# openSX70-dongle_v6-3-dual-led.net
KiCad netlist of a schematic drawn in EAGLE
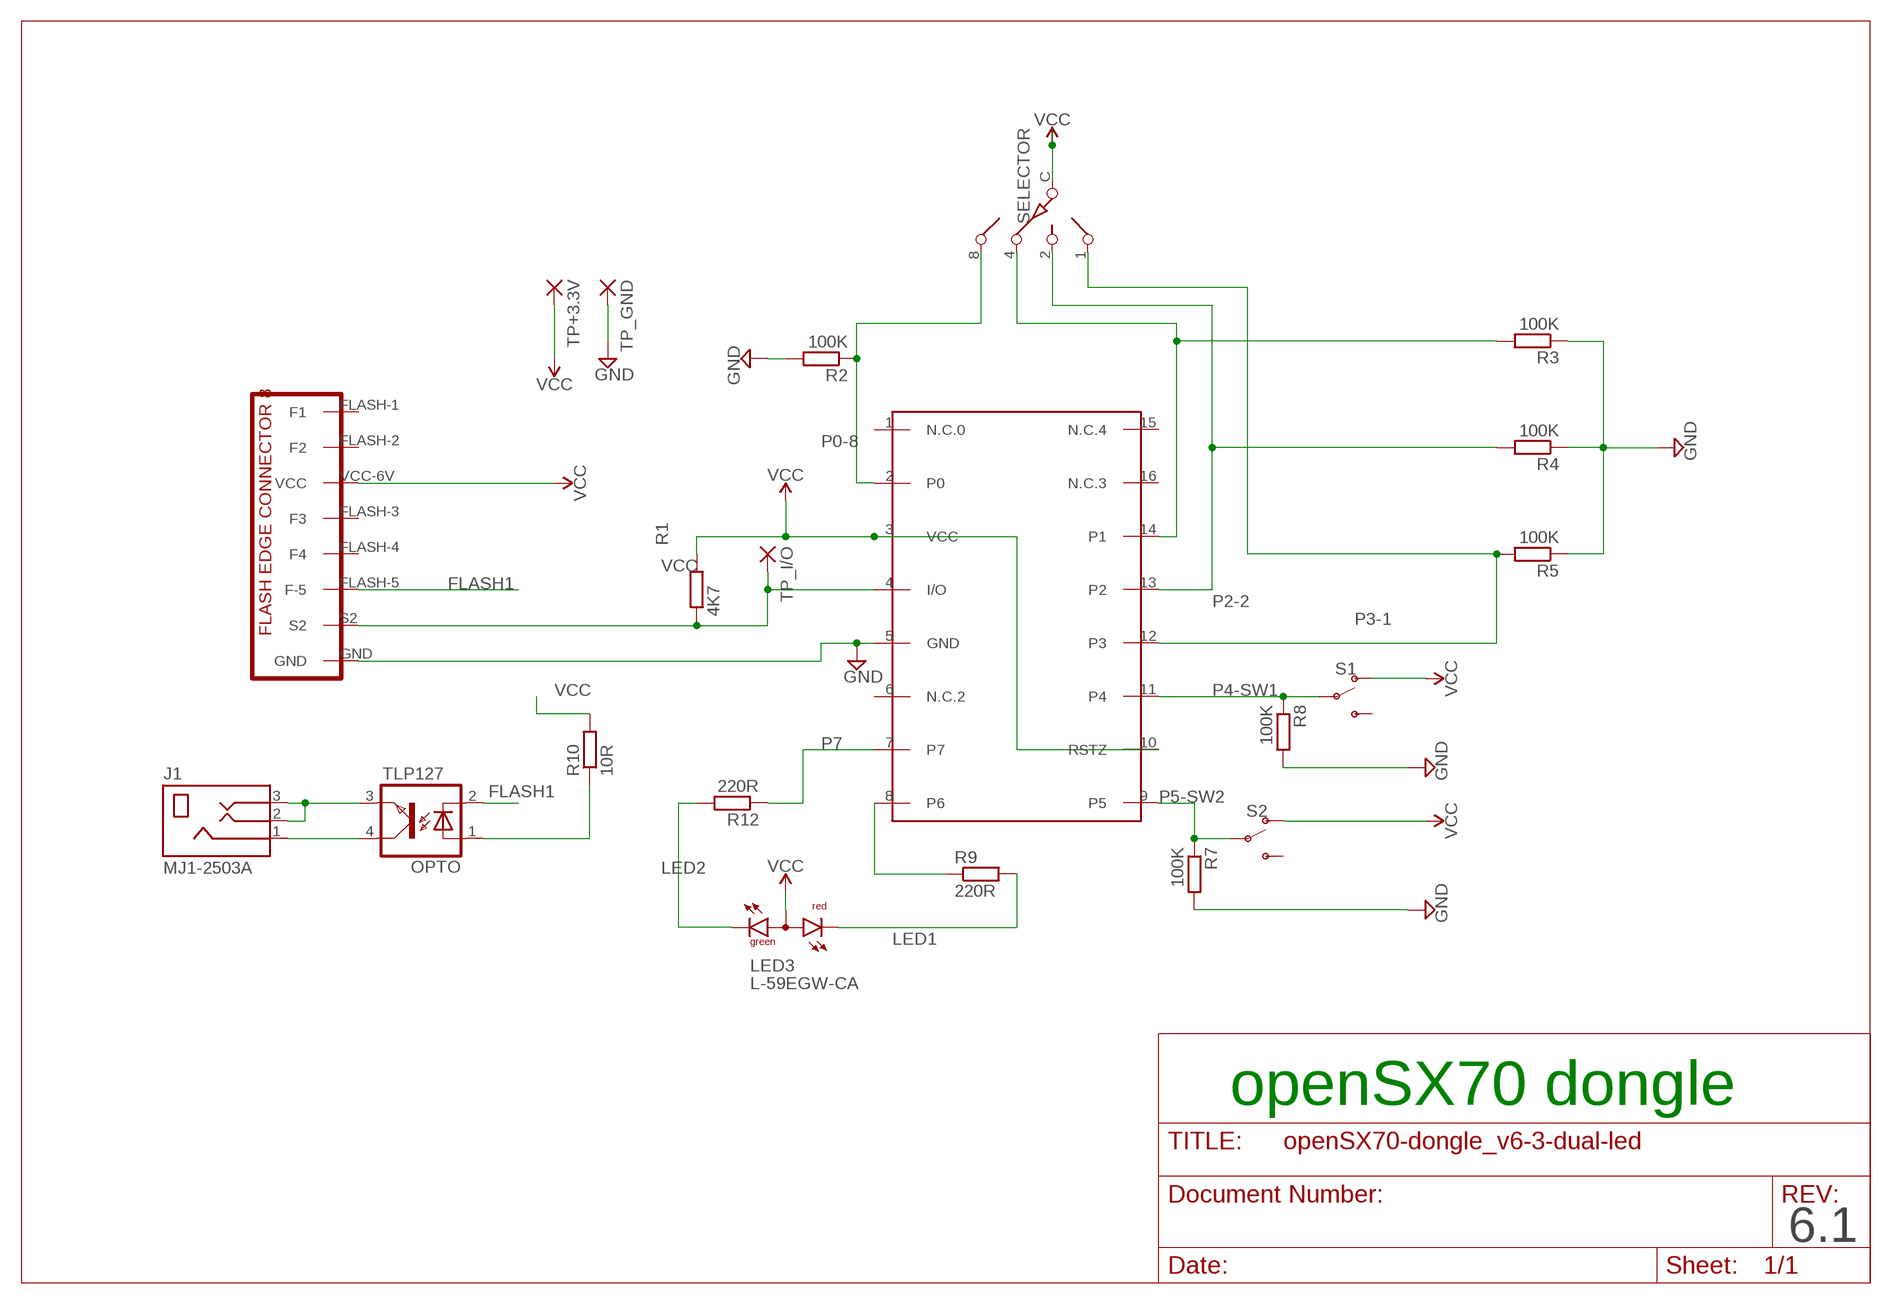
[diagram p0: schematic, sheet 1]

(export (version "E")
  (design (tool "Eeschema 10.0.6"))
  (components
    (comp (ref "DS2408")
      (value "DS2408")
      (footprint "eagle-import:SO16")
      (libsource (lib "eagle-import") (part "DS2408"))
    )
    (comp (ref "J1")
      (value "MJ1-2503A")
      (footprint "eagle-import:CUI_MJ1-2503A")
      (fields (field (name "DIGI-KEY_PART_NUMBER") "CP1-2503AM-ND") (field (name "MF") "CUI Inc."))
      (libsource (lib "eagle-import") (part "MJ1-2503A"))
    )
    (comp (ref "LED3")
      (value "L-59EGW-CA")
      (footprint "eagle-import:L-59EGW-CA")
      (libsource (lib "eagle-import") (part "L-59EGW-CA"))
    )
    (comp (ref "OPTO")
      (value "TLP127")
      (footprint "eagle-import:SO-4")
      (libsource (lib "eagle-import") (part "TLP127"))
    )
    (comp (ref "R1")
      (value "4K7")
      (footprint "eagle-import:R0603")
      (libsource (lib "eagle-import") (part "R-EU_R0603"))
    )
    (comp (ref "R2")
      (value "100K")
      (footprint "eagle-import:R0603")
      (libsource (lib "eagle-import") (part "R-EU_R0603"))
    )
    (comp (ref "R3")
      (value "100K")
      (footprint "eagle-import:R0603")
      (libsource (lib "eagle-import") (part "R-EU_R0603"))
    )
    (comp (ref "R4")
      (value "100K")
      (footprint "eagle-import:R0603")
      (libsource (lib "eagle-import") (part "R-EU_R0603"))
    )
    (comp (ref "R5")
      (value "100K")
      (footprint "eagle-import:R0603")
      (libsource (lib "eagle-import") (part "R-EU_R0603"))
    )
    (comp (ref "R7")
      (value "100K")
      (footprint "eagle-import:R0603")
      (libsource (lib "eagle-import") (part "R-EU_R0603"))
    )
    (comp (ref "R8")
      (value "100K")
      (footprint "eagle-import:R0603")
      (libsource (lib "eagle-import") (part "R-EU_R0603"))
    )
    (comp (ref "R9")
      (value "220R")
      (footprint "eagle-import:R0603")
      (libsource (lib "eagle-import") (part "R-EU_R0603"))
    )
    (comp (ref "R10")
      (value "10R")
      (footprint "eagle-import:R0603")
      (libsource (lib "eagle-import") (part "resistor_348_R-EU_R0603"))
    )
    (comp (ref "R12")
      (value "220R")
      (footprint "eagle-import:R0603")
      (libsource (lib "eagle-import") (part "R-EU_R0603"))
    )
    (comp (ref "S1")
      (value "SWITCH-SPDT-SMD-RIGHT-ANGLE")
      (footprint "eagle-import:SWITCH_SPST_SMD_A")
      (libsource (lib "eagle-import") (part "SWITCH-SPDT-SMD-RIGHT-ANGLE"))
    )
    (comp (ref "S2")
      (value "SWITCH-SPDT-SMD-RIGHT-ANGLE")
      (footprint "eagle-import:SWITCH_SPST_SMD_A")
      (libsource (lib "eagle-import") (part "SWITCH-SPDT-SMD-RIGHT-ANGLE"))
    )
    (comp (ref "SELECTOR")
      (value "SW-C16")
      (footprint "eagle-import:SW-C16")
      (libsource (lib "eagle-import") (part "SW-C16"))
    )
    (comp (ref "TP+3.3V")
      (value "SMD2")
      (footprint "eagle-import:SMD1,27-2,54")
      (libsource (lib "eagle-import") (part "SMD2"))
    )
    (comp (ref "TP_GND")
      (value "SMD2")
      (footprint "eagle-import:SMD1,27-2,54")
      (libsource (lib "eagle-import") (part "SMD2"))
    )
    (comp (ref "TP_I/O")
      (value "SMD2")
      (footprint "eagle-import:SMD1,27-2,54")
      (libsource (lib "eagle-import") (part "SMD2"))
    )
    (comp (ref "U$2")
      (value "SX70-FLASH-EDGE8-MALE-PROPER")
      (footprint "eagle-import:SX70-FLASH-EDGE8")
      (libsource (lib "eagle-import") (part "SX70-FLASH-EDGE8-MALE-PROPER"))
    )
  )
  (nets
    (net (code "1") (name "/FLASH1") (class "Default")
      (node (ref "OPTO") (pin "2") (pinfunction "C_2") (pintype "passive"))
      (node (ref "U$2") (pin "FLASH-5") (pinfunction "F-5_FLASH-5") (pintype "bidirectional"))
    )
    (net (code "2") (name "/LED1") (class "Default")
      (node (ref "LED3") (pin "1") (pinfunction "CR_1") (pintype "passive"))
      (node (ref "R9") (pin "2") (pinfunction "2_2") (pintype "passive"))
    )
    (net (code "3") (name "/LED2") (class "Default")
      (node (ref "LED3") (pin "3") (pinfunction "CG_3") (pintype "passive"))
      (node (ref "R12") (pin "2") (pinfunction "2_2") (pintype "passive"))
    )
    (net (code "4") (name "/P0-8") (class "Default")
      (node (ref "DS2408") (pin "2") (pinfunction "P0_2") (pintype "bidirectional"))
      (node (ref "R2") (pin "1") (pinfunction "1_1") (pintype "passive"))
      (node (ref "SELECTOR") (pin "8") (pinfunction "8_8") (pintype "passive"))
    )
    (net (code "5") (name "/P2-2") (class "Default")
      (node (ref "DS2408") (pin "13") (pinfunction "P2_13") (pintype "bidirectional"))
      (node (ref "R4") (pin "2") (pinfunction "2_2") (pintype "passive"))
      (node (ref "SELECTOR") (pin "2") (pinfunction "2_2") (pintype "passive"))
    )
    (net (code "6") (name "/P3-1") (class "Default")
      (node (ref "DS2408") (pin "12") (pinfunction "P3_12") (pintype "bidirectional"))
      (node (ref "R5") (pin "2") (pinfunction "2_2") (pintype "passive"))
      (node (ref "SELECTOR") (pin "1") (pinfunction "1_1") (pintype "passive"))
    )
    (net (code "7") (name "/P4-SW1") (class "Default")
      (node (ref "DS2408") (pin "11") (pinfunction "P4_11") (pintype "bidirectional"))
      (node (ref "R8") (pin "1") (pinfunction "1_1") (pintype "passive"))
      (node (ref "S1") (pin "2") (pinfunction "P_2") (pintype "passive"))
    )
    (net (code "8") (name "/P5-SW2") (class "Default")
      (node (ref "DS2408") (pin "9") (pinfunction "P5_9") (pintype "bidirectional"))
      (node (ref "R7") (pin "1") (pinfunction "1_1") (pintype "passive"))
      (node (ref "S2") (pin "2") (pinfunction "P_2") (pintype "passive"))
    )
    (net (code "9") (name "/P7") (class "Default")
      (node (ref "DS2408") (pin "7") (pinfunction "P7_7") (pintype "bidirectional"))
      (node (ref "R12") (pin "1") (pinfunction "1_1") (pintype "passive"))
    )
    (net (code "10") (name "GND") (class "Default")
      (node (ref "DS2408") (pin "5") (pinfunction "GND_5") (pintype "bidirectional"))
      (node (ref "R2") (pin "2") (pinfunction "2_2") (pintype "passive"))
      (node (ref "R3") (pin "1") (pinfunction "1_1") (pintype "passive"))
      (node (ref "R4") (pin "1") (pinfunction "1_1") (pintype "passive"))
      (node (ref "R5") (pin "1") (pinfunction "1_1") (pintype "passive"))
      (node (ref "R7") (pin "2") (pinfunction "2_2") (pintype "passive"))
      (node (ref "R8") (pin "2") (pinfunction "2_2") (pintype "passive"))
      (node (ref "TP_GND") (pin "1") (pinfunction "P_1") (pintype "passive"))
      (node (ref "U$2") (pin "GND") (pinfunction "GND_GND") (pintype "bidirectional"))
    )
    (net (code "11") (name "Net-(DS2408-I{slash}O)") (class "Default")
      (node (ref "DS2408") (pin "4") (pinfunction "I/O_4") (pintype "bidirectional"))
      (node (ref "R1") (pin "1") (pinfunction "1_1") (pintype "passive"))
      (node (ref "TP_I/O") (pin "1") (pinfunction "P_1") (pintype "passive"))
      (node (ref "U$2") (pin "S2") (pinfunction "S2_S2") (pintype "bidirectional"))
    )
    (net (code "12") (name "Net-(DS2408-P1)") (class "Default")
      (node (ref "DS2408") (pin "14") (pinfunction "P1_14") (pintype "bidirectional"))
      (node (ref "R3") (pin "2") (pinfunction "2_2") (pintype "passive"))
      (node (ref "SELECTOR") (pin "4") (pinfunction "4_4") (pintype "passive"))
    )
    (net (code "13") (name "Net-(DS2408-P6)") (class "Default")
      (node (ref "DS2408") (pin "8") (pinfunction "P6_8") (pintype "bidirectional"))
      (node (ref "R9") (pin "1") (pinfunction "1_1") (pintype "passive"))
    )
    (net (code "14") (name "Net-(OPTO-A)") (class "Default")
      (node (ref "OPTO") (pin "1") (pinfunction "A_1") (pintype "passive"))
      (node (ref "R10") (pin "1") (pinfunction "1_1") (pintype "passive"))
    )
    (net (code "15") (name "Net-(OPTO-COL)") (class "Default")
      (node (ref "J1") (pin "1") (pinfunction "1_1") (pintype "passive"))
      (node (ref "OPTO") (pin "4") (pinfunction "COL_4") (pintype "passive"))
    )
    (net (code "16") (name "Net-(OPTO-EMIT)") (class "Default")
      (node (ref "J1") (pin "2") (pinfunction "2_2") (pintype "passive"))
      (node (ref "J1") (pin "3") (pinfunction "3_3") (pintype "passive"))
      (node (ref "OPTO") (pin "3") (pinfunction "EMIT_3") (pintype "passive"))
    )
    (net (code "17") (name "VCC") (class "Default")
      (node (ref "DS2408") (pin "10") (pinfunction "RSTZ_10") (pintype "bidirectional"))
      (node (ref "DS2408") (pin "3") (pinfunction "VCC_3") (pintype "bidirectional"))
      (node (ref "LED3") (pin "2") (pinfunction "A_2") (pintype "passive"))
      (node (ref "R1") (pin "2") (pinfunction "2_2") (pintype "passive"))
      (node (ref "R10") (pin "2") (pinfunction "2_2") (pintype "passive"))
      (node (ref "S1") (pin "1") (pinfunction "O_1") (pintype "passive"))
      (node (ref "S2") (pin "1") (pinfunction "O_1") (pintype "passive"))
      (node (ref "SELECTOR") (pin "C") (pinfunction "C_C") (pintype "passive"))
      (node (ref "TP+3.3V") (pin "1") (pinfunction "P_1") (pintype "passive"))
      (node (ref "U$2") (pin "VCC-6V") (pinfunction "VCC_VCC-6V") (pintype "bidirectional"))
    )
    (net (code "18") (name "unconnected-(DS2408-N.C.0-Pad1)") (class "Default")
      (node (ref "DS2408") (pin "1") (pinfunction "N.C.0_1") (pintype "bidirectional"))
    )
    (net (code "19") (name "unconnected-(DS2408-N.C.2-Pad6)") (class "Default")
      (node (ref "DS2408") (pin "6") (pinfunction "N.C.2_6") (pintype "bidirectional"))
    )
    (net (code "20") (name "unconnected-(DS2408-N.C.3-Pad16)") (class "Default")
      (node (ref "DS2408") (pin "16") (pinfunction "N.C.3_16") (pintype "bidirectional"))
    )
    (net (code "21") (name "unconnected-(DS2408-N.C.4-Pad15)") (class "Default")
      (node (ref "DS2408") (pin "15") (pinfunction "N.C.4_15") (pintype "bidirectional"))
    )
    (net (code "22") (name "unconnected-(S1-S-Pad3)") (class "Default")
      (node (ref "S1") (pin "3") (pinfunction "S_3") (pintype "passive"))
    )
    (net (code "23") (name "unconnected-(S2-S-Pad3)") (class "Default")
      (node (ref "S2") (pin "3") (pinfunction "S_3") (pintype "passive"))
    )
    (net (code "24") (name "unconnected-(U$2-F1-PadFLASH-1)") (class "Default")
      (node (ref "U$2") (pin "FLASH-1") (pinfunction "F1_FLASH-1") (pintype "bidirectional"))
    )
    (net (code "25") (name "unconnected-(U$2-F2-PadFLASH-2)") (class "Default")
      (node (ref "U$2") (pin "FLASH-2") (pinfunction "F2_FLASH-2") (pintype "bidirectional"))
    )
    (net (code "26") (name "unconnected-(U$2-F3-PadFLASH-3)") (class "Default")
      (node (ref "U$2") (pin "FLASH-3") (pinfunction "F3_FLASH-3") (pintype "bidirectional"))
    )
    (net (code "27") (name "unconnected-(U$2-F4-PadFLASH-4)") (class "Default")
      (node (ref "U$2") (pin "FLASH-4") (pinfunction "F4_FLASH-4") (pintype "bidirectional"))
    )
  )
)
